# SCH_W-F-FC-HX2X.net
KiCad netlist of a schematic drawn in Altium Designer
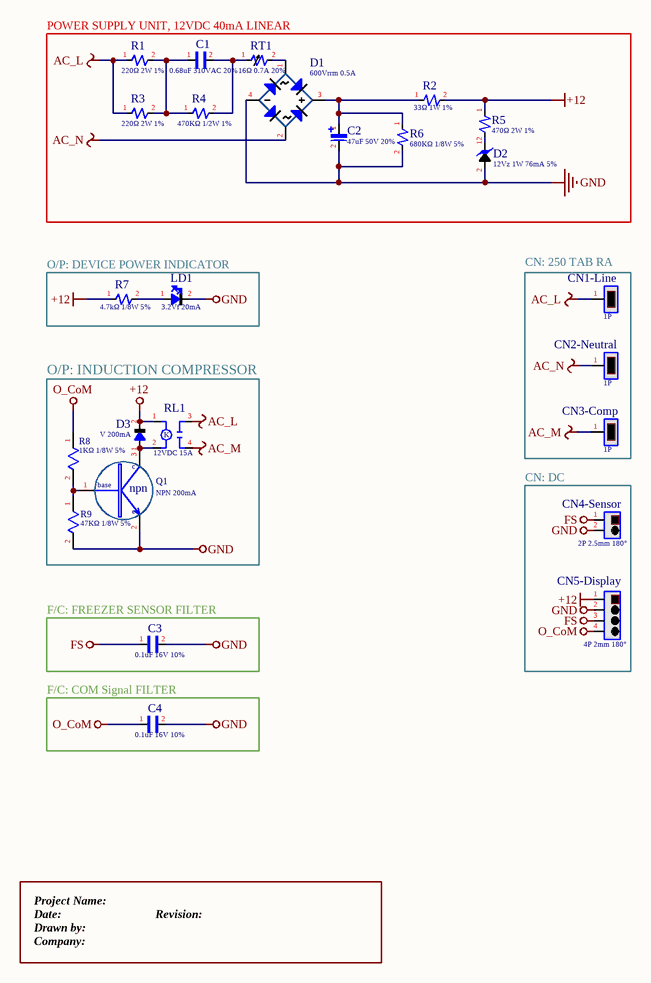
[diagram p0: SCH_W-F-FC-HX2X.SchDoc]

(export (version "E")
  (design (tool "Eeschema 10.0.6"))
  (components
    (comp (ref "C1")
      (value "0.68uF 310VAC 20%")
      (footprint "C_X2_18X10X15.8_P15")
      (description "684K310V, P=15 18*9.5*15.5, Climate-category: 40/110/56")
      (libsource (lib "RBM_ALTIUM_SCH_LIBRARY") (part "Capacitor{gt}{gt} Non-Polar"))
    )
    (comp (ref "C2")
      (value "47uF 50V 20%")
      (footprint "C_Radial_Ø6.3*11mm_P2.5")
      (description "Aluminum Electrolytic Capacitor, Through Hole, ØDxL=6.3*11mm Pitch=2.5mm")
      (libsource (lib "RBM_ALTIUM_SCH_LIBRARY") (part "Capacitor{gt}{gt} Polar"))
    )
    (comp (ref "C3")
      (value "0.1uF 16V 10%")
      (footprint "C_0805")
      (description "Multilayer Ceramic Capacitors, SMD 0805")
      (libsource (lib "RBM_ALTIUM_SCH_LIBRARY") (part "Capacitor{gt}{gt} Non-Polar"))
    )
    (comp (ref "C4")
      (value "0.1uF 16V 10%")
      (footprint "C_0805")
      (description "Multilayer Ceramic Capacitors, SMD 0805")
      (libsource (lib "RBM_ALTIUM_SCH_LIBRARY") (part "Capacitor{gt}{gt} Non-Polar"))
    )
    (comp (ref "CN1-Line")
      (value "1P")
      (footprint "CN_Tab Terminal 250 series (Right Angle)")
      (description "6.3mm PCB Tab Terminal (Right Angle)")
      (libsource (lib "RBM_ALTIUM_SCH_LIBRARY") (part "Connector{gt}{gt} 1Pin"))
    )
    (comp (ref "CN2-Neutral")
      (value "1P")
      (footprint "CN_Tab Terminal 250 series (Right Angle)")
      (description "6.3mm PCB Tab Terminal (Right Angle)")
      (libsource (lib "RBM_ALTIUM_SCH_LIBRARY") (part "Connector{gt}{gt} 1Pin"))
    )
    (comp (ref "CN3-Comp")
      (value "1P")
      (footprint "CN_Tab Terminal 250 series (Right Angle)")
      (description "6.3mm PCB Tab Terminal (Right Angle)")
      (libsource (lib "RBM_ALTIUM_SCH_LIBRARY") (part "Connector{gt}{gt} 1Pin"))
    )
    (comp (ref "CN4-Sensor")
      (value "2P 2.5mm 180°")
      (footprint "CN_B2B-XH-A_RED")
      (description "A2512WV-XP, 2Pins, 2.5mmPitch, 180° Wafer, RED, Through Hole")
      (libsource (lib "RBM_ALTIUM_SCH_LIBRARY") (part "Connector{gt}{gt} 2Pins"))
    )
    (comp (ref "CN5-Display")
      (value "4P 2mm 180°")
      (footprint "CN_4P_A2001WV-XP-180DEG")
      (description "A2001WV-XP, 4Pins, 2mmPitch, 180° Wafer, White, , Through Hole")
      (libsource (lib "RBM_ALTIUM_SCH_LIBRARY") (part "Connector{gt}{gt} 4Pins"))
    )
    (comp (ref "D1")
      (value "600Vrrm 0.5A")
      (footprint "D_SMD_MB6S")
      (description "MB6S, SOIC, ON-SEMICONDUCTOR")
      (libsource (lib "RBM_ALTIUM_SCH_LIBRARY") (part "Diode{gt}{gt} Bridge Rectifier"))
    )
    (comp (ref "D2")
      (value "12Vz 1W 76mA 5%")
      (footprint "D_SMD_LL-41")
      (description "ZM4742, MELF SILICON PLANAR POWER ZENER DIODES, LL-41")
      (libsource (lib "RBM_ALTIUM_SCH_LIBRARY") (part "Diode{gt}{gt} Zener"))
    )
    (comp (ref "D3")
      (value "V 200mA")
      (footprint "D_SOT-23-3_200mA")
      (description "BAS19, SOT-23-3")
      (libsource (lib "RBM_ALTIUM_SCH_LIBRARY") (part "Diode{gt}{gt} General Purpose"))
    )
    (comp (ref "LD1")
      (value "3.2Vf 20mA")
      (footprint "LED_3x5_P2.5")
      (description "RED, Through hole, ØDxH=3x5mm Pitch=2.5mm")
      (libsource (lib "RBM_ALTIUM_SCH_LIBRARY") (part "LED{gt}{gt} General Purpose"))
    )
    (comp (ref "Q1")
      (value "NPN 200mA")
      (footprint "Q_SOT-23-3_NPN_BC847")
      (description "BC847, SOT-23-3")
      (libsource (lib "RBM_SCH-Lib_16-Apr-19") (part "BJT_npn"))
    )
    (comp (ref "R1")
      (value "220Ω 2W 1%")
      (footprint "R_Axial_P15")
      (description "Metal Oxide Film Resistor, Through Hole Axial, L=12, øD=5, H=28, ød=0.6, Flame Proof")
      (libsource (lib "RBM_ALTIUM_SCH_LIBRARY") (part "Resistor{gt}{gt} General Purpose"))
    )
    (comp (ref "R2")
      (value "33Ω 1W 1%")
      (footprint "R_Axial_P15")
      (description "Metal Oxide Film Resistor, Through Hole Axial, L=10, øD=4, H=28, ød=0.5, Flame Proof")
      (libsource (lib "RBM_ALTIUM_SCH_LIBRARY") (part "Resistor{gt}{gt} General Purpose"))
    )
    (comp (ref "R3")
      (value "220Ω 2W 1%")
      (footprint "R_Axial_P15")
      (description "Metal Oxide Film Resistor, Through Hole Axial, L=12, øD=5, H=28, ød=0.6, Flame Proof")
      (libsource (lib "RBM_ALTIUM_SCH_LIBRARY") (part "Resistor{gt}{gt} General Purpose"))
    )
    (comp (ref "R4")
      (value "470KΩ 1/2W 1%")
      (footprint "R_Axial_P10")
      (description "Metal Oxide Film Resistor, Through Hole Axial, L=7, øD=2.5, H=28, ød=0.48, Flame Proof")
      (libsource (lib "RBM_ALTIUM_SCH_LIBRARY") (part "Resistor{gt}{gt} General Purpose"))
    )
    (comp (ref "R5")
      (value "470Ω 2W 1%")
      (footprint "R_Axial_P15")
      (description "Metal Oxide Film Resistor, Through Hole Axial, L=12, øD=5, H=28, ød=0.6, Flame Proof")
      (libsource (lib "RBM_ALTIUM_SCH_LIBRARY") (part "Resistor{gt}{gt} General Purpose"))
    )
    (comp (ref "R6")
      (value "680KΩ 1/8W 5%")
      (footprint "R_0805")
      (description "Chip-Resistor, SMD 0805, , RoHS")
      (libsource (lib "RBM_ALTIUM_SCH_LIBRARY") (part "Resistor{gt}{gt} General Purpose"))
    )
    (comp (ref "R7")
      (value "4.7kΩ 1/8W 5%")
      (footprint "R_0805")
      (description "Chip-Resistor, SMD 0805, , RoHS")
      (libsource (lib "RBM_ALTIUM_SCH_LIBRARY") (part "Resistor{gt}{gt} General Purpose"))
    )
    (comp (ref "R8")
      (value "1KΩ 1/8W 5%")
      (footprint "R_0805")
      (description "Chip-Resistor, SMD 0805, , RoHS")
      (libsource (lib "RBM_SCH-Lib_16-Apr-19") (part "Resistor"))
    )
    (comp (ref "R9")
      (value "47KΩ 1/8W 5%")
      (footprint "R_0805")
      (description "Chip-Resistor, SMD 0805, , RoHS")
      (libsource (lib "RBM_SCH-Lib_16-Apr-19") (part "Resistor"))
    )
    (comp (ref "RL1")
      (value "12VDC 15A")
      (footprint "RL_SPST_15ARelay_AZ943-1AH-12DE")
      (description "Zettler AZ943–1CH–12DE")
      (libsource (lib "RBM_ALTIUM_SCH_LIBRARY") (part "Relay{gt}{gt} SPST"))
    )
    (comp (ref "RT1")
      (value "16Ω 0.7A 20%")
      (footprint "NTC_5mmPitch")
      (description "16D-7, NTC, Pitch 5mm")
      (libsource (lib "RBM_ALTIUM_SCH_LIBRARY") (part "Thermistor{gt}{gt} NTC"))
    )
  )
  (nets
    (net (code "1") (name "+12") (class "Default")
      (node (ref "CN5-Display") (pin "1") (pinfunction "1_1") (pintype "passive"))
      (node (ref "D3") (pin "2") (pinfunction "K_2") (pintype "passive"))
      (node (ref "R2") (pin "2") (pinfunction "2_2") (pintype "passive"))
      (node (ref "R5") (pin "1") (pinfunction "1_1") (pintype "passive"))
      (node (ref "R7") (pin "1") (pinfunction "1_1") (pintype "passive"))
      (node (ref "RL1") (pin "1") (pinfunction "1_1") (pintype "passive"))
    )
    (net (code "2") (name "AC_L") (class "Default")
      (node (ref "CN1-Line") (pin "1") (pinfunction "1_1") (pintype "passive"))
      (node (ref "R1") (pin "1") (pinfunction "1_1") (pintype "passive"))
      (node (ref "R3") (pin "1") (pinfunction "1_1") (pintype "passive"))
      (node (ref "RL1") (pin "3") (pinfunction "3_3") (pintype "passive"))
    )
    (net (code "3") (name "AC_M") (class "Default")
      (node (ref "CN3-Comp") (pin "1") (pinfunction "1_1") (pintype "passive"))
      (node (ref "RL1") (pin "4") (pinfunction "4_4") (pintype "passive"))
    )
    (net (code "4") (name "AC_N") (class "Default")
      (node (ref "CN2-Neutral") (pin "1") (pinfunction "1_1") (pintype "passive"))
      (node (ref "D1") (pin "2") (pinfunction "AC_2") (pintype "passive"))
    )
    (net (code "5") (name "FS") (class "Default")
      (node (ref "C3") (pin "1") (pinfunction "1_1") (pintype "passive"))
      (node (ref "CN4-Sensor") (pin "1") (pinfunction "1_1") (pintype "passive"))
      (node (ref "CN5-Display") (pin "3") (pinfunction "3_3") (pintype "passive"))
    )
    (net (code "6") (name "GND") (class "Default")
      (node (ref "C2") (pin "2") (pinfunction "2_2") (pintype "passive"))
      (node (ref "C3") (pin "2") (pinfunction "2_2") (pintype "passive"))
      (node (ref "C4") (pin "2") (pinfunction "2_2") (pintype "passive"))
      (node (ref "CN4-Sensor") (pin "2") (pinfunction "2_2") (pintype "passive"))
      (node (ref "CN5-Display") (pin "2") (pinfunction "2_2") (pintype "passive"))
      (node (ref "D1") (pin "4") (pinfunction "vss_4") (pintype "passive"))
      (node (ref "D2") (pin "2") (pinfunction "K_2") (pintype "passive"))
      (node (ref "LD1") (pin "2") (pinfunction "vss_2") (pintype "passive"))
      (node (ref "Q1") (pin "2") (pinfunction "Emitter_2") (pintype "passive"))
      (node (ref "R6") (pin "2") (pinfunction "2_2") (pintype "passive"))
      (node (ref "R9") (pin "2") (pinfunction "2_2") (pintype "passive"))
    )
    (net (code "7") (name "Net-(C1-Pad1)") (class "Default")
      (node (ref "C1") (pin "1") (pinfunction "1_1") (pintype "passive"))
      (node (ref "R1") (pin "2") (pinfunction "2_2") (pintype "passive"))
      (node (ref "R3") (pin "2") (pinfunction "2_2") (pintype "passive"))
      (node (ref "R4") (pin "1") (pinfunction "1_1") (pintype "passive"))
    )
    (net (code "8") (name "Net-(C1-Pad2)") (class "Default")
      (node (ref "C1") (pin "2") (pinfunction "2_2") (pintype "passive"))
      (node (ref "R4") (pin "2") (pinfunction "2_2") (pintype "passive"))
      (node (ref "RT1") (pin "1") (pinfunction "1_1") (pintype "passive"))
    )
    (net (code "9") (name "Net-(D1-AC-Pad1)") (class "Default")
      (node (ref "D1") (pin "1") (pinfunction "AC_1") (pintype "passive"))
      (node (ref "RT1") (pin "2") (pinfunction "2_2") (pintype "passive"))
    )
    (net (code "10") (name "Net-(D1-VCC)") (class "Default")
      (node (ref "C2") (pin "1") (pinfunction "1_1") (pintype "passive"))
      (node (ref "D1") (pin "3") (pinfunction "VCC_3") (pintype "passive"))
      (node (ref "R2") (pin "1") (pinfunction "1_1") (pintype "passive"))
      (node (ref "R6") (pin "1") (pinfunction "1_1") (pintype "passive"))
    )
    (net (code "11") (name "Net-(D2-A)") (class "Default")
      (node (ref "D2") (pin "1") (pinfunction "A_1") (pintype "passive"))
      (node (ref "R5") (pin "2") (pinfunction "2_2") (pintype "passive"))
    )
    (net (code "12") (name "Net-(D3-A)") (class "Default")
      (node (ref "D3") (pin "1") (pinfunction "A_1") (pintype "passive"))
      (node (ref "Q1") (pin "3") (pinfunction "Collector_3") (pintype "passive"))
      (node (ref "RL1") (pin "2") (pinfunction "2_2") (pintype "passive"))
    )
    (net (code "13") (name "Net-(LD1-vdd)") (class "Default")
      (node (ref "LD1") (pin "1") (pinfunction "vdd_1") (pintype "passive"))
      (node (ref "R7") (pin "2") (pinfunction "2_2") (pintype "passive"))
    )
    (net (code "14") (name "Net-(Q1-Base)") (class "Default")
      (node (ref "Q1") (pin "1") (pinfunction "Base_1") (pintype "passive"))
      (node (ref "R8") (pin "2") (pinfunction "2_2") (pintype "passive"))
      (node (ref "R9") (pin "1") (pinfunction "1_1") (pintype "passive"))
    )
    (net (code "15") (name "O_CoM") (class "Default")
      (node (ref "C4") (pin "1") (pinfunction "1_1") (pintype "passive"))
      (node (ref "CN5-Display") (pin "4") (pinfunction "4_4") (pintype "passive"))
      (node (ref "R8") (pin "1") (pinfunction "1_1") (pintype "passive"))
    )
  )
)
